# main.net
KiCad netlist of a schematic drawn in EAGLE
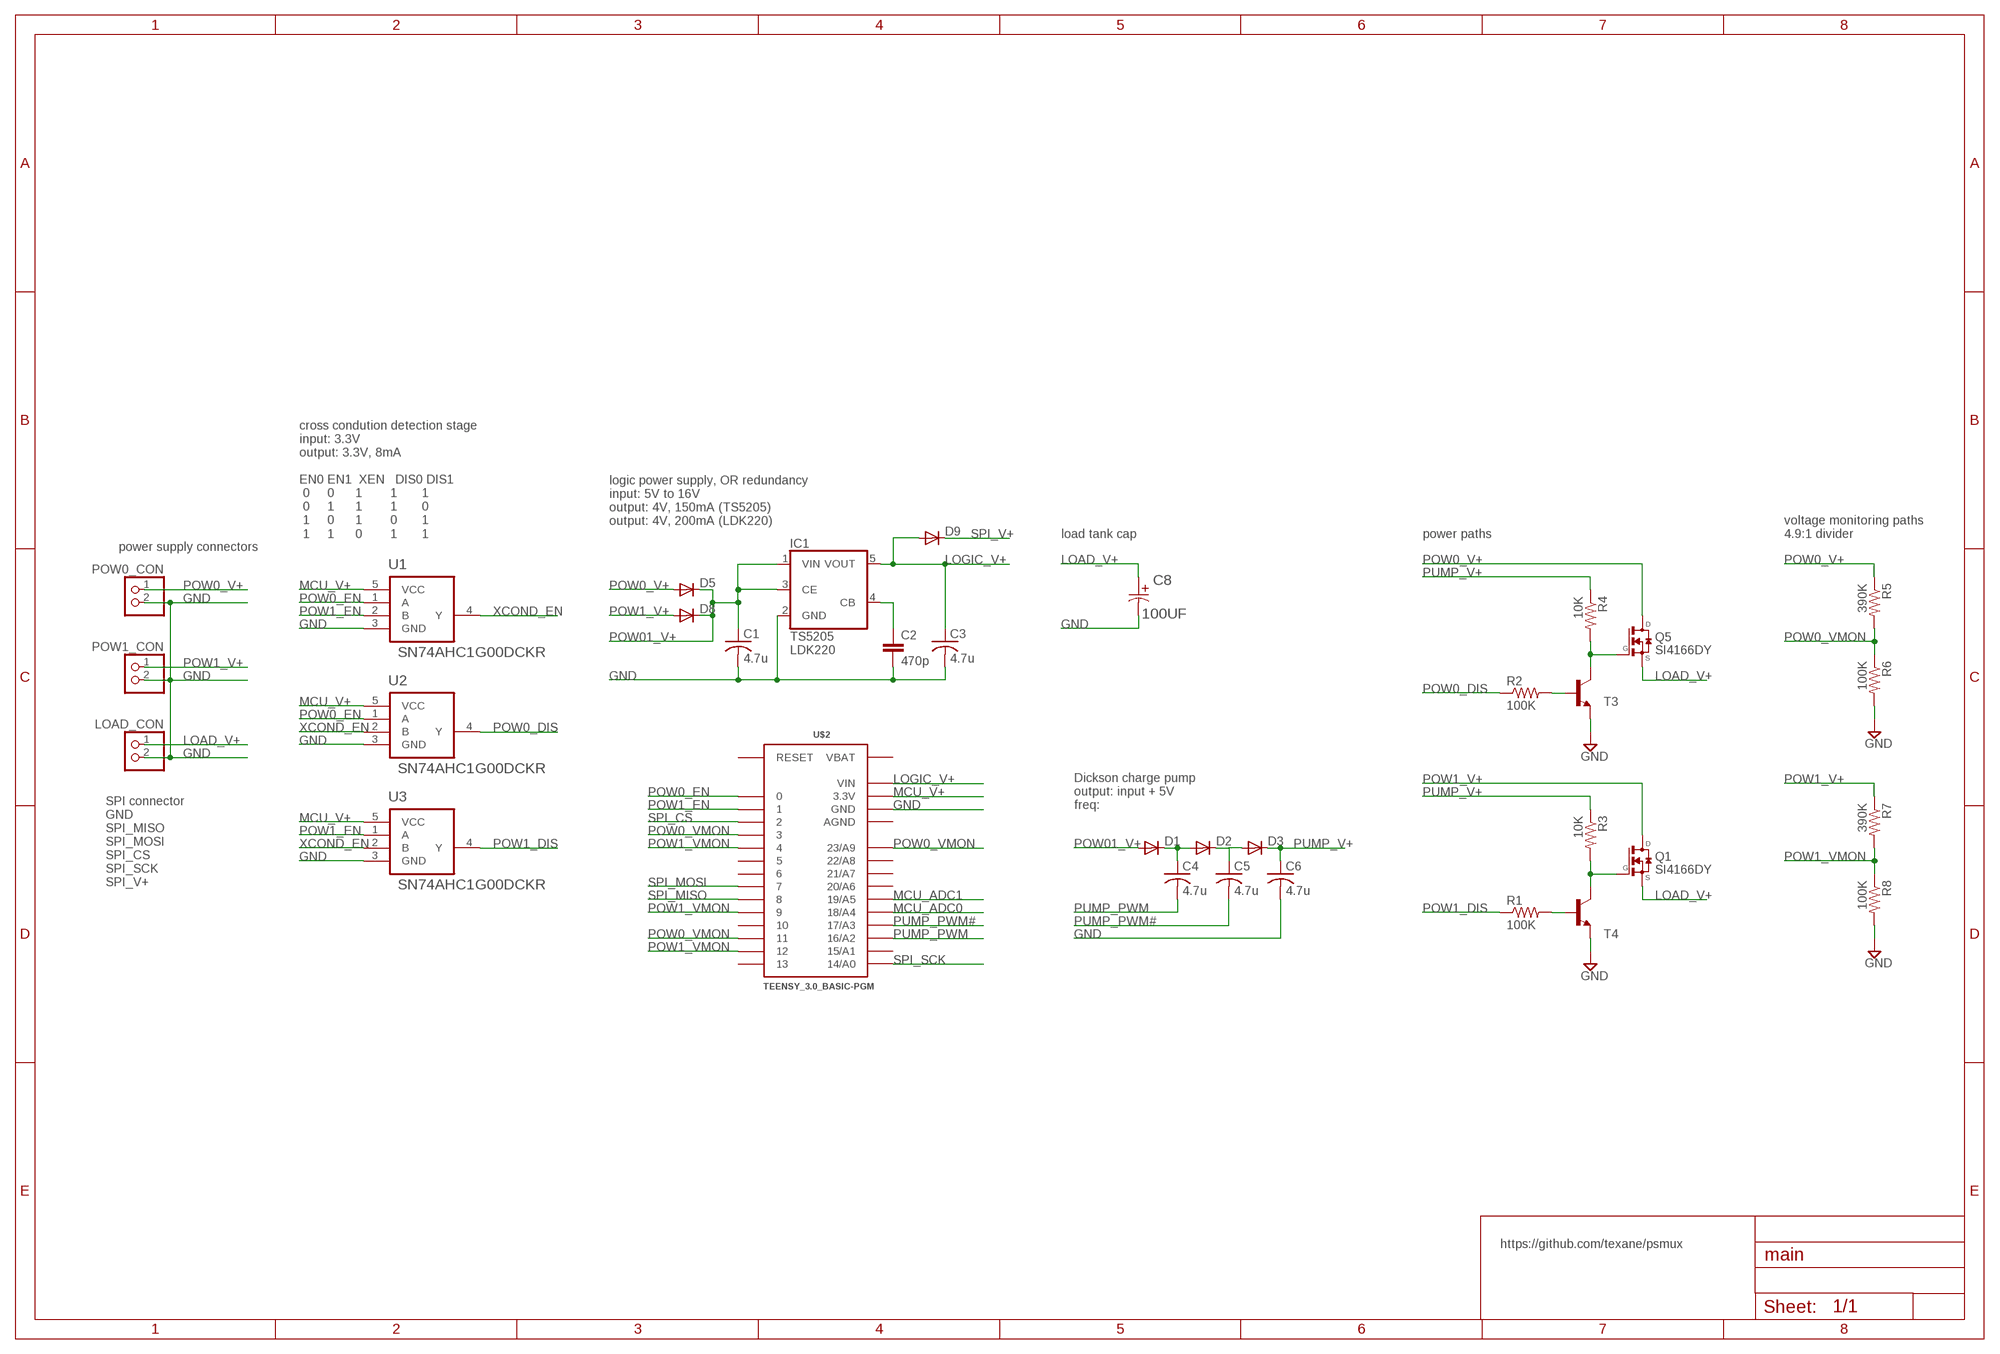
[diagram p0: schematic, sheet 1]

(export (version "E")
  (design (tool "Eeschema 10.0.6"))
  (components
    (comp (ref "C1")
      (value "4.7u")
      (footprint "eagle-import:C1210K")
      (libsource (lib "eagle-import") (part "C-USC1210K"))
    )
    (comp (ref "C2")
      (value "470p")
      (footprint "eagle-import:C0805K")
      (libsource (lib "eagle-import") (part "C-EUC0805K"))
    )
    (comp (ref "C3")
      (value "4.7u")
      (footprint "eagle-import:C1210K")
      (libsource (lib "eagle-import") (part "C-USC1210K"))
    )
    (comp (ref "C4")
      (value "4.7u")
      (footprint "eagle-import:C1210K")
      (libsource (lib "eagle-import") (part "C-USC1210K"))
    )
    (comp (ref "C5")
      (value "4.7u")
      (footprint "eagle-import:C1210K")
      (libsource (lib "eagle-import") (part "C-USC1210K"))
    )
    (comp (ref "C6")
      (value "4.7u")
      (footprint "eagle-import:C1210K")
      (libsource (lib "eagle-import") (part "C-USC1210K"))
    )
    (comp (ref "C8")
      (value "100UF")
      (footprint "eagle-import:CAPAE660X800N")
      (fields (field (name "MPN") "EEE-FK1E101XP") (field (name "TOLERANCE") "±20 %"))
      (libsource (lib "eagle-import") (part "EEE--CASE-D8FK1E101XP"))
    )
    (comp (ref "D1")
      (value "DIODE-DO214AC")
      (footprint "eagle-import:DO214AC")
      (libsource (lib "eagle-import") (part "DIODE-DO214AC"))
    )
    (comp (ref "D2")
      (value "DIODE-DO214AC")
      (footprint "eagle-import:DO214AC")
      (libsource (lib "eagle-import") (part "DIODE-DO214AC"))
    )
    (comp (ref "D3")
      (value "DIODE-DO214AC")
      (footprint "eagle-import:DO214AC")
      (libsource (lib "eagle-import") (part "DIODE-DO214AC"))
    )
    (comp (ref "D5")
      (value "DIODE-DO214AC")
      (footprint "eagle-import:DO214AC")
      (libsource (lib "eagle-import") (part "DIODE-DO214AC"))
    )
    (comp (ref "D8")
      (value "DIODE-DO214AC")
      (footprint "eagle-import:DO214AC")
      (libsource (lib "eagle-import") (part "DIODE-DO214AC"))
    )
    (comp (ref "D9")
      (value "DIODE-DO214AC")
      (footprint "eagle-import:DO214AC")
      (libsource (lib "eagle-import") (part "DIODE-DO214AC"))
    )
    (comp (ref "IC1")
      (value "TS5205")
      (footprint "eagle-import:SOT25")
      (libsource (lib "eagle-import") (part "TS5205"))
    )
    (comp (ref "LOAD_CON")
      (value "PINHD-1X2")
      (footprint "eagle-import:1X02")
      (libsource (lib "eagle-import") (part "PINHD-1X2"))
    )
    (comp (ref "POW0_CON")
      (value "PINHD-1X2")
      (footprint "eagle-import:1X02")
      (libsource (lib "eagle-import") (part "PINHD-1X2"))
    )
    (comp (ref "POW1_CON")
      (value "PINHD-1X2")
      (footprint "eagle-import:1X02")
      (libsource (lib "eagle-import") (part "PINHD-1X2"))
    )
    (comp (ref "Q1")
      (value "SI4840DY")
      (footprint "eagle-import:SO08-E3")
      (libsource (lib "eagle-import") (part "SI4840DY"))
    )
    (comp (ref "Q5")
      (value "SI4840DY")
      (footprint "eagle-import:SO08-E3")
      (libsource (lib "eagle-import") (part "SI4840DY"))
    )
    (comp (ref "R1")
      (value "100K")
      (footprint "eagle-import:M0805")
      (libsource (lib "eagle-import") (part "R-US_M0805"))
    )
    (comp (ref "R2")
      (value "100K")
      (footprint "eagle-import:M0805")
      (libsource (lib "eagle-import") (part "R-US_M0805"))
    )
    (comp (ref "R3")
      (value "10K")
      (footprint "eagle-import:M0805")
      (libsource (lib "eagle-import") (part "R-US_M0805"))
    )
    (comp (ref "R4")
      (value "10K")
      (footprint "eagle-import:M0805")
      (libsource (lib "eagle-import") (part "R-US_M0805"))
    )
    (comp (ref "R5")
      (value "390K")
      (footprint "eagle-import:M0805")
      (libsource (lib "eagle-import") (part "R-US_M0805"))
    )
    (comp (ref "R6")
      (value "100K")
      (footprint "eagle-import:M0805")
      (libsource (lib "eagle-import") (part "R-US_M0805"))
    )
    (comp (ref "R7")
      (value "390K")
      (footprint "eagle-import:M0805")
      (libsource (lib "eagle-import") (part "R-US_M0805"))
    )
    (comp (ref "R8")
      (value "100K")
      (footprint "eagle-import:M0805")
      (libsource (lib "eagle-import") (part "R-US_M0805"))
    )
    (comp (ref "T3")
      (value "BC817-40-NPN-SOT23-BEC")
      (footprint "eagle-import:SOT23-BEC")
      (libsource (lib "eagle-import") (part "-NPN-SOT23-BECBC817-40"))
    )
    (comp (ref "T4")
      (value "BC817-40-NPN-SOT23-BEC")
      (footprint "eagle-import:SOT23-BEC")
      (libsource (lib "eagle-import") (part "-NPN-SOT23-BECBC817-40"))
    )
    (comp (ref "U$2")
      (value "TEENSY_3.0_BASIC-PGM")
      (footprint "eagle-import:TEENSY_3.0_BASIC-PGM")
      (libsource (lib "eagle-import") (part "TEENSY_3.0_BASIC-PGM"))
    )
    (comp (ref "U1")
      (value "SN74AHC1G00DCKR")
      (footprint "eagle-import:SOT65P210X110-5N")
      (libsource (lib "eagle-import") (part "SN74AHC1G00DCKR"))
    )
    (comp (ref "U2")
      (value "SN74AHC1G00DCKR")
      (footprint "eagle-import:SOT65P210X110-5N")
      (libsource (lib "eagle-import") (part "SN74AHC1G00DCKR"))
    )
    (comp (ref "U3")
      (value "SN74AHC1G00DCKR")
      (footprint "eagle-import:SOT65P210X110-5N")
      (libsource (lib "eagle-import") (part "SN74AHC1G00DCKR"))
    )
  )
  (nets
    (net (code "1") (name "/AGND") (class "Default")
      (node (ref "U$2") (pin "AGND") (pinfunction "AGND_AGND") (pintype "power_in"))
    )
    (net (code "2") (name "/LOAD_V+") (class "Default")
      (node (ref "C8") (pin "1") (pinfunction "1_1") (pintype "passive"))
      (node (ref "LOAD_CON") (pin "1") (pinfunction "1_1") (pintype "passive"))
      (node (ref "Q1") (pin "1-3") (pinfunction "S_1-3") (pintype "passive"))
      (node (ref "Q5") (pin "1-3") (pinfunction "S_1-3") (pintype "passive"))
    )
    (net (code "3") (name "/LOGIC_V+") (class "Default")
      (node (ref "C3") (pin "1") (pinfunction "1_1") (pintype "passive"))
      (node (ref "D9") (pin "A") (pinfunction "A_A") (pintype "passive"))
      (node (ref "IC1") (pin "5") (pinfunction "VOUT_5") (pintype "passive"))
      (node (ref "U$2") (pin "VIN") (pinfunction "VIN_VIN") (pintype "power_in"))
    )
    (net (code "4") (name "/MCU_ADC0") (class "Default")
      (node (ref "U$2") (pin "18/A4") (pinfunction "18/A4_18/A4") (pintype "bidirectional"))
    )
    (net (code "5") (name "/MCU_ADC1") (class "Default")
      (node (ref "U$2") (pin "19/A5") (pinfunction "19/A5_19/A5") (pintype "bidirectional"))
    )
    (net (code "6") (name "/MCU_V+") (class "Default")
      (node (ref "U$2") (pin "3.3V") (pinfunction "3.3V_3.3V") (pintype "power_in"))
      (node (ref "U$2") (pin "3.3V1") (pinfunction "3.3V_3.3V1") (pintype "power_in"))
      (node (ref "U1") (pin "5") (pinfunction "VCC_5") (pintype "power_in"))
      (node (ref "U2") (pin "5") (pinfunction "VCC_5") (pintype "power_in"))
      (node (ref "U3") (pin "5") (pinfunction "VCC_5") (pintype "power_in"))
    )
    (net (code "7") (name "/POW0_DIS") (class "Default")
      (node (ref "R2") (pin "1") (pinfunction "1_1") (pintype "passive"))
      (node (ref "U2") (pin "4") (pinfunction "Y_4") (pintype "output"))
    )
    (net (code "8") (name "/POW0_EN") (class "Default")
      (node (ref "U$2") (pin "0") (pinfunction "0_0") (pintype "bidirectional"))
      (node (ref "U1") (pin "1") (pinfunction "A_1") (pintype "input"))
      (node (ref "U2") (pin "1") (pinfunction "A_1") (pintype "input"))
    )
    (net (code "9") (name "/POW0_V+") (class "Default")
      (node (ref "D5") (pin "A") (pinfunction "A_A") (pintype "passive"))
      (node (ref "POW0_CON") (pin "1") (pinfunction "1_1") (pintype "passive"))
      (node (ref "Q5") (pin "5-8") (pinfunction "D_5-8") (pintype "passive"))
      (node (ref "R5") (pin "1") (pinfunction "1_1") (pintype "passive"))
    )
    (net (code "10") (name "/POW0_VMON") (class "Default")
      (node (ref "R5") (pin "2") (pinfunction "2_2") (pintype "passive"))
      (node (ref "R6") (pin "1") (pinfunction "1_1") (pintype "passive"))
      (node (ref "U$2") (pin "11") (pinfunction "11_11") (pintype "bidirectional"))
      (node (ref "U$2") (pin "23/A9") (pinfunction "23/A9_23/A9") (pintype "bidirectional"))
      (node (ref "U$2") (pin "3") (pinfunction "3_3") (pintype "bidirectional"))
    )
    (net (code "11") (name "/POW1_DIS") (class "Default")
      (node (ref "R1") (pin "1") (pinfunction "1_1") (pintype "passive"))
      (node (ref "U3") (pin "4") (pinfunction "Y_4") (pintype "output"))
    )
    (net (code "12") (name "/POW1_EN") (class "Default")
      (node (ref "U$2") (pin "1") (pinfunction "1_1") (pintype "bidirectional"))
      (node (ref "U1") (pin "2") (pinfunction "B_2") (pintype "input"))
      (node (ref "U3") (pin "1") (pinfunction "A_1") (pintype "input"))
    )
    (net (code "13") (name "/POW01_V+") (class "Default")
      (node (ref "C1") (pin "1") (pinfunction "1_1") (pintype "passive"))
      (node (ref "D1") (pin "A") (pinfunction "A_A") (pintype "passive"))
      (node (ref "D5") (pin "C") (pinfunction "C_C") (pintype "passive"))
      (node (ref "D8") (pin "C") (pinfunction "C_C") (pintype "passive"))
      (node (ref "IC1") (pin "1") (pinfunction "VIN_1") (pintype "input"))
      (node (ref "IC1") (pin "3") (pinfunction "CE_3") (pintype "input"))
    )
    (net (code "14") (name "/POW1_V+") (class "Default")
      (node (ref "D8") (pin "A") (pinfunction "A_A") (pintype "passive"))
      (node (ref "POW1_CON") (pin "1") (pinfunction "1_1") (pintype "passive"))
      (node (ref "Q1") (pin "5-8") (pinfunction "D_5-8") (pintype "passive"))
      (node (ref "R7") (pin "1") (pinfunction "1_1") (pintype "passive"))
    )
    (net (code "15") (name "/POW1_VMON") (class "Default")
      (node (ref "R7") (pin "2") (pinfunction "2_2") (pintype "passive"))
      (node (ref "R8") (pin "1") (pinfunction "1_1") (pintype "passive"))
      (node (ref "U$2") (pin "12") (pinfunction "12_12") (pintype "bidirectional"))
      (node (ref "U$2") (pin "4") (pinfunction "4_4") (pintype "bidirectional"))
      (node (ref "U$2") (pin "9") (pinfunction "9_9") (pintype "bidirectional"))
    )
    (net (code "16") (name "/PUMP_PWM") (class "Default")
      (node (ref "C4") (pin "2") (pinfunction "2_2") (pintype "passive"))
      (node (ref "U$2") (pin "16/A2") (pinfunction "16/A2_16/A2") (pintype "bidirectional"))
    )
    (net (code "17") (name "/PUMP_PWM#") (class "Default")
      (node (ref "C5") (pin "2") (pinfunction "2_2") (pintype "passive"))
      (node (ref "U$2") (pin "17/A3") (pinfunction "17/A3_17/A3") (pintype "bidirectional"))
    )
    (net (code "18") (name "/PUMP_V+") (class "Default")
      (node (ref "C6") (pin "1") (pinfunction "1_1") (pintype "passive"))
      (node (ref "D3") (pin "C") (pinfunction "C_C") (pintype "passive"))
      (node (ref "R3") (pin "1") (pinfunction "1_1") (pintype "passive"))
      (node (ref "R4") (pin "1") (pinfunction "1_1") (pintype "passive"))
    )
    (net (code "19") (name "/SPI_CS") (class "Default")
      (node (ref "U$2") (pin "2") (pinfunction "2_2") (pintype "bidirectional"))
    )
    (net (code "20") (name "/SPI_MISO") (class "Default")
      (node (ref "U$2") (pin "8") (pinfunction "8_8") (pintype "bidirectional"))
    )
    (net (code "21") (name "/SPI_MOSI") (class "Default")
      (node (ref "U$2") (pin "7") (pinfunction "7_7") (pintype "bidirectional"))
    )
    (net (code "22") (name "/SPI_SCK") (class "Default")
      (node (ref "U$2") (pin "14/A0") (pinfunction "14/A0_14/A0") (pintype "bidirectional"))
    )
    (net (code "23") (name "/SPI_V+") (class "Default")
      (node (ref "D9") (pin "C") (pinfunction "C_C") (pintype "passive"))
    )
    (net (code "24") (name "/VBAT") (class "Default")
      (node (ref "U$2") (pin "VBAT") (pinfunction "VBAT_VBAT") (pintype "power_in"))
    )
    (net (code "25") (name "/XCOND_EN") (class "Default")
      (node (ref "U1") (pin "4") (pinfunction "Y_4") (pintype "output"))
      (node (ref "U2") (pin "2") (pinfunction "B_2") (pintype "input"))
      (node (ref "U3") (pin "2") (pinfunction "B_2") (pintype "input"))
    )
    (net (code "26") (name "GND") (class "Default")
      (node (ref "C1") (pin "2") (pinfunction "2_2") (pintype "passive"))
      (node (ref "C2") (pin "2") (pinfunction "2_2") (pintype "passive"))
      (node (ref "C3") (pin "2") (pinfunction "2_2") (pintype "passive"))
      (node (ref "C6") (pin "2") (pinfunction "2_2") (pintype "passive"))
      (node (ref "C8") (pin "2") (pinfunction "2_2") (pintype "passive"))
      (node (ref "IC1") (pin "2") (pinfunction "GND_2") (pintype "passive"))
      (node (ref "LOAD_CON") (pin "2") (pinfunction "2_2") (pintype "passive"))
      (node (ref "POW0_CON") (pin "2") (pinfunction "2_2") (pintype "passive"))
      (node (ref "POW1_CON") (pin "2") (pinfunction "2_2") (pintype "passive"))
      (node (ref "R6") (pin "2") (pinfunction "2_2") (pintype "passive"))
      (node (ref "R8") (pin "2") (pinfunction "2_2") (pintype "passive"))
      (node (ref "T3") (pin "E") (pinfunction "E_E") (pintype "passive"))
      (node (ref "T4") (pin "E") (pinfunction "E_E") (pintype "passive"))
      (node (ref "U$2") (pin "GND") (pinfunction "GND_GND") (pintype "power_in"))
      (node (ref "U$2") (pin "GND1") (pinfunction "GND_GND1") (pintype "power_in"))
      (node (ref "U1") (pin "3") (pinfunction "GND_3") (pintype "passive"))
      (node (ref "U2") (pin "3") (pinfunction "GND_3") (pintype "passive"))
      (node (ref "U3") (pin "3") (pinfunction "GND_3") (pintype "passive"))
    )
    (net (code "27") (name "Net-(C4-Pad1)") (class "Default")
      (node (ref "C4") (pin "1") (pinfunction "1_1") (pintype "passive"))
      (node (ref "D1") (pin "C") (pinfunction "C_C") (pintype "passive"))
      (node (ref "D2") (pin "A") (pinfunction "A_A") (pintype "passive"))
    )
    (net (code "28") (name "Net-(C5-Pad1)") (class "Default")
      (node (ref "C5") (pin "1") (pinfunction "1_1") (pintype "passive"))
      (node (ref "D2") (pin "C") (pinfunction "C_C") (pintype "passive"))
      (node (ref "D3") (pin "A") (pinfunction "A_A") (pintype "passive"))
    )
    (net (code "29") (name "Net-(IC1-CB)") (class "Default")
      (node (ref "C2") (pin "1") (pinfunction "1_1") (pintype "passive"))
      (node (ref "IC1") (pin "4") (pinfunction "CB_4") (pintype "input"))
    )
    (net (code "30") (name "Net-(Q1-G)") (class "Default")
      (node (ref "Q1") (pin "4") (pinfunction "G_4") (pintype "passive"))
      (node (ref "R3") (pin "2") (pinfunction "2_2") (pintype "passive"))
      (node (ref "T4") (pin "C") (pinfunction "C_C") (pintype "passive"))
    )
    (net (code "31") (name "Net-(Q5-G)") (class "Default")
      (node (ref "Q5") (pin "4") (pinfunction "G_4") (pintype "passive"))
      (node (ref "R4") (pin "2") (pinfunction "2_2") (pintype "passive"))
      (node (ref "T3") (pin "C") (pinfunction "C_C") (pintype "passive"))
    )
    (net (code "32") (name "Net-(R1-Pad2)") (class "Default")
      (node (ref "R1") (pin "2") (pinfunction "2_2") (pintype "passive"))
      (node (ref "T4") (pin "B") (pinfunction "B_B") (pintype "passive"))
    )
    (net (code "33") (name "Net-(R2-Pad2)") (class "Default")
      (node (ref "R2") (pin "2") (pinfunction "2_2") (pintype "passive"))
      (node (ref "T3") (pin "B") (pinfunction "B_B") (pintype "passive"))
    )
    (net (code "34") (name "unconnected-(U$2-Pad5)") (class "Default")
      (node (ref "U$2") (pin "5") (pinfunction "5_5") (pintype "bidirectional"))
    )
    (net (code "35") (name "unconnected-(U$2-Pad6)") (class "Default")
      (node (ref "U$2") (pin "6") (pinfunction "6_6") (pintype "bidirectional"))
    )
    (net (code "36") (name "unconnected-(U$2-Pad10)") (class "Default")
      (node (ref "U$2") (pin "10") (pinfunction "10_10") (pintype "bidirectional"))
    )
    (net (code "37") (name "unconnected-(U$2-Pad13)") (class "Default")
      (node (ref "U$2") (pin "13") (pinfunction "13_13") (pintype "bidirectional"))
    )
    (net (code "38") (name "unconnected-(U$2-Pad15{slash}A1)") (class "Default")
      (node (ref "U$2") (pin "15/A1") (pinfunction "15/A1_15/A1") (pintype "bidirectional"))
    )
    (net (code "39") (name "unconnected-(U$2-Pad20{slash}A6)") (class "Default")
      (node (ref "U$2") (pin "20/A6") (pinfunction "20/A6_20/A6") (pintype "bidirectional"))
    )
    (net (code "40") (name "unconnected-(U$2-Pad21{slash}A7)") (class "Default")
      (node (ref "U$2") (pin "21/A7") (pinfunction "21/A7_21/A7") (pintype "bidirectional"))
    )
    (net (code "41") (name "unconnected-(U$2-Pad22{slash}A8)") (class "Default")
      (node (ref "U$2") (pin "22/A8") (pinfunction "22/A8_22/A8") (pintype "bidirectional"))
    )
    (net (code "42") (name "unconnected-(U$2-PadRESET)") (class "Default")
      (node (ref "U$2") (pin "RESET") (pinfunction "RESET_RESET") (pintype "bidirectional"))
    )
  )
)
